# Sheet2.net
KiCad netlist of a schematic drawn in Altium Designer
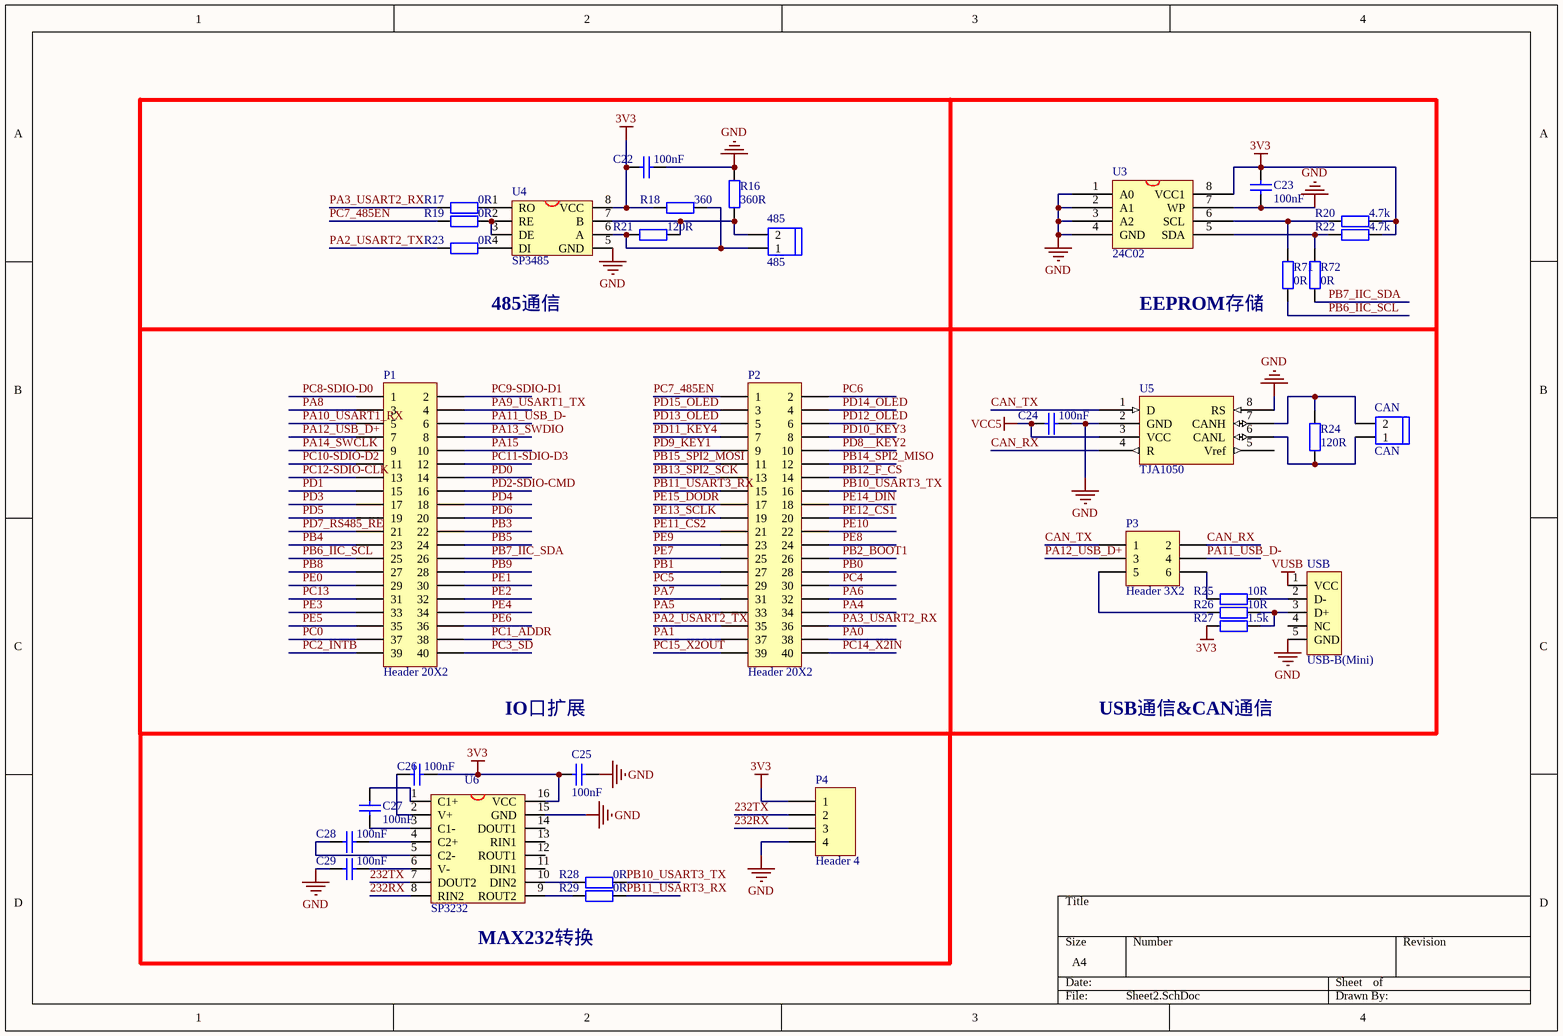
[diagram p0: Sheet2.SchDoc]

(export (version "E")
  (design (tool "Eeschema 10.0.6"))
  (components
    (comp (ref "485")
      (value "485")
      (footprint "HEAD2L-0.8")
      (libsource (lib "Explorer STM32F407封装库") (part "HEAD2"))
    )
    (comp (ref "C22")
      (value "100nF")
      (footprint "LC-0603_C")
      (description "无极性电容")
      (fields (field (name "PUBLISHER") "Altium Limited"))
      (libsource (lib "liu_2016") (part "Cap"))
    )
    (comp (ref "C23")
      (value "100nF")
      (footprint "LC-0603_C")
      (description "无极性电容")
      (fields (field (name "PUBLISHER") "Altium Limited"))
      (libsource (lib "liu_2016") (part "Cap"))
    )
    (comp (ref "C24")
      (value "100nF")
      (footprint "LC-0603_C")
      (description "无极性电容")
      (fields (field (name "PUBLISHER") "Altium Limited"))
      (libsource (lib "liu_2016") (part "Cap"))
    )
    (comp (ref "C25")
      (value "100nF")
      (footprint "LC-0603_C")
      (description "无极性电容")
      (fields (field (name "PUBLISHER") "Altium Limited"))
      (libsource (lib "liu_2016") (part "Cap"))
    )
    (comp (ref "C26")
      (value "100nF")
      (footprint "LC-0603_C")
      (description "无极性电容")
      (fields (field (name "PUBLISHER") "Altium Limited"))
      (libsource (lib "liu_2016") (part "Cap"))
    )
    (comp (ref "C27")
      (value "100nF")
      (footprint "LC-0603_C")
      (description "无极性电容")
      (fields (field (name "PUBLISHER") "Altium Limited"))
      (libsource (lib "liu_2016") (part "Cap"))
    )
    (comp (ref "C28")
      (value "100nF")
      (footprint "LC-0603_C")
      (description "无极性电容")
      (fields (field (name "PUBLISHER") "Altium Limited"))
      (libsource (lib "liu_2016") (part "Cap"))
    )
    (comp (ref "C29")
      (value "100nF")
      (footprint "LC-0603_C")
      (description "无极性电容")
      (fields (field (name "PUBLISHER") "Altium Limited"))
      (libsource (lib "liu_2016") (part "Cap"))
    )
    (comp (ref "CAN")
      (value "CAN")
      (footprint "CON_2_5.08B")
      (libsource (lib "Explorer STM32F407封装库") (part "HEAD2"))
    )
    (comp (ref "P1")
      (value "Header 20X2")
      (footprint "HDR2X20")
      (description "Header, 20-Pin, Dual row")
      (fields (field (name "PUBLISHER") "Altium Limited"))
      (libsource (lib "Sparks") (part "Header 20X2"))
    )
    (comp (ref "P2")
      (value "Header 20X2")
      (footprint "HDR2X20")
      (description "Header, 20-Pin, Dual row")
      (fields (field (name "PUBLISHER") "Altium Limited"))
      (libsource (lib "Sparks") (part "Header 20X2"))
    )
    (comp (ref "P3")
      (value "Header 3X2")
      (footprint "HDR2X3")
      (description "Header, 3-Pin, Dual row")
      (fields (field (name "PUBLISHER") "Altium Limited"))
      (libsource (lib "Sparks") (part "Header 3X2"))
    )
    (comp (ref "P4")
      (value "Header 4")
      (footprint "HDR1X4")
      (description "Header, 4-Pin")
      (fields (field (name "PUBLISHER") "Altium Limited"))
      (libsource (lib "Sparks") (part "Header 4"))
    )
    (comp (ref "R16")
      (value "360R")
      (footprint "LC-0603_R")
      (description "贴片电阻")
      (fields (field (name "PUBLISHER") "Altium Limited"))
      (libsource (lib "") (part "Res1_1"))
    )
    (comp (ref "R17")
      (value "0R")
      (footprint "LC-0603_R")
      (description "贴片电阻")
      (fields (field (name "PUBLISHER") "Altium Limited"))
      (libsource (lib "liu_2016") (part "Res1"))
    )
    (comp (ref "R18")
      (value "360")
      (footprint "LC-0603_R")
      (description "贴片电阻")
      (fields (field (name "PUBLISHER") "Altium Limited"))
      (libsource (lib "liu_2016") (part "Res1"))
    )
    (comp (ref "R19")
      (value "0R")
      (footprint "LC-0603_R")
      (description "贴片电阻")
      (fields (field (name "PUBLISHER") "Altium Limited"))
      (libsource (lib "liu_2016") (part "Res1"))
    )
    (comp (ref "R20")
      (value "4.7k")
      (footprint "LC-0603_R")
      (description "贴片电阻")
      (fields (field (name "PUBLISHER") "Altium Limited"))
      (libsource (lib "liu_2016") (part "Res1"))
    )
    (comp (ref "R21")
      (value "120R")
      (footprint "LC-0603_R")
      (description "贴片电阻")
      (fields (field (name "PUBLISHER") "Altium Limited"))
      (libsource (lib "liu_2016") (part "Res1"))
    )
    (comp (ref "R22")
      (value "4.7k")
      (footprint "LC-0603_R")
      (description "贴片电阻")
      (fields (field (name "PUBLISHER") "Altium Limited"))
      (libsource (lib "liu_2016") (part "Res1"))
    )
    (comp (ref "R23")
      (value "0R")
      (footprint "LC-0603_R")
      (description "贴片电阻")
      (fields (field (name "PUBLISHER") "Altium Limited"))
      (libsource (lib "liu_2016") (part "Res1"))
    )
    (comp (ref "R24")
      (value "120R")
      (footprint "LC-0603_R")
      (description "贴片电阻")
      (fields (field (name "PUBLISHER") "Altium Limited"))
      (libsource (lib "") (part "Res1_1"))
    )
    (comp (ref "R25")
      (value "10R")
      (footprint "LC-0603_R")
      (description "贴片电阻")
      (fields (field (name "PUBLISHER") "Altium Limited"))
      (libsource (lib "") (part "Res1_2"))
    )
    (comp (ref "R26")
      (value "10R")
      (footprint "LC-0603_R")
      (description "贴片电阻")
      (fields (field (name "PUBLISHER") "Altium Limited"))
      (libsource (lib "") (part "Res1_2"))
    )
    (comp (ref "R27")
      (value "1.5k")
      (footprint "LC-0603_R")
      (description "贴片电阻")
      (fields (field (name "PUBLISHER") "Altium Limited"))
      (libsource (lib "") (part "Res1_2"))
    )
    (comp (ref "R28")
      (value "0R")
      (footprint "LC-0603_R")
      (description "贴片电阻")
      (fields (field (name "PUBLISHER") "Altium Limited"))
      (libsource (lib "liu_2016") (part "Res1"))
    )
    (comp (ref "R29")
      (value "0R")
      (footprint "LC-0603_R")
      (description "贴片电阻")
      (fields (field (name "PUBLISHER") "Altium Limited"))
      (libsource (lib "liu_2016") (part "Res1"))
    )
    (comp (ref "R71")
      (value "0R")
      (footprint "LC-0603_R")
      (description "贴片电阻")
      (libsource (lib "Miscellaneous Devices LC") (part "0603 1.5KΩ (1501) 1%"))
    )
    (comp (ref "R72")
      (value "0R")
      (footprint "LC-0603_R")
      (description "贴片电阻")
      (libsource (lib "Miscellaneous Devices LC") (part "0603 1.5KΩ (1501) 1%"))
    )
    (comp (ref "U3")
      (value "24C02")
      (footprint "SO-8")
      (libsource (lib "Explorer STM32F407封装库") (part "24C256"))
    )
    (comp (ref "U4")
      (value "SP3485")
      (footprint "SO-8")
      (libsource (lib "Explorer STM32F407封装库") (part "MAX3485"))
    )
    (comp (ref "U5")
      (value "TJA1050")
      (footprint "SO-8")
      (libsource (lib "Explorer STM32F407封装库") (part "SN65HVD230D"))
    )
    (comp (ref "U6")
      (value "SP3232")
      (footprint "SO-16")
      (libsource (lib "Explorer STM32F407封装库") (part "MAX3232"))
    )
    (comp (ref "USB")
      (value "USB-B(Mini)")
      (footprint "USB/SM0.8-6H5")
      (libsource (lib "Explorer STM32F407封装库") (part "USB5"))
    )
  )
  (nets
    (net (code "1") (name "/232RX") (class "Default")
      (node (ref "P4") (pin "3") (pinfunction "3_3") (pintype "passive"))
      (node (ref "U6") (pin "8") (pinfunction "RIN2_8") (pintype "passive"))
    )
    (net (code "2") (name "/232TX") (class "Default")
      (node (ref "P4") (pin "2") (pinfunction "2_2") (pintype "passive"))
      (node (ref "U6") (pin "7") (pinfunction "DOUT2_7") (pintype "passive"))
    )
    (net (code "3") (name "/CAN_RX") (class "Default")
      (node (ref "P3") (pin "2") (pinfunction "2_2") (pintype "passive"))
      (node (ref "U5") (pin "4") (pinfunction "R_4") (pintype "output"))
    )
    (net (code "4") (name "/CAN_TX") (class "Default")
      (node (ref "P3") (pin "1") (pinfunction "1_1") (pintype "passive"))
      (node (ref "U5") (pin "1") (pinfunction "D_1") (pintype "input"))
    )
    (net (code "5") (name "/PA0") (class "Default")
      (node (ref "P2") (pin "38") (pinfunction "38_38") (pintype "passive"))
    )
    (net (code "6") (name "/PA1") (class "Default")
      (node (ref "P2") (pin "37") (pinfunction "37_37") (pintype "passive"))
    )
    (net (code "7") (name "/PA2_USART2_TX") (class "Default")
      (node (ref "P2") (pin "35") (pinfunction "35_35") (pintype "passive"))
      (node (ref "R23") (pin "2") (pinfunction "2_2") (pintype "passive"))
    )
    (net (code "8") (name "/PA3_USART2_RX") (class "Default")
      (node (ref "P2") (pin "36") (pinfunction "36_36") (pintype "passive"))
      (node (ref "R17") (pin "2") (pinfunction "2_2") (pintype "passive"))
    )
    (net (code "9") (name "/PA4") (class "Default")
      (node (ref "P2") (pin "34") (pinfunction "34_34") (pintype "passive"))
    )
    (net (code "10") (name "/PA5") (class "Default")
      (node (ref "P2") (pin "33") (pinfunction "33_33") (pintype "passive"))
    )
    (net (code "11") (name "/PA6") (class "Default")
      (node (ref "P2") (pin "32") (pinfunction "32_32") (pintype "passive"))
    )
    (net (code "12") (name "/PA7") (class "Default")
      (node (ref "P2") (pin "31") (pinfunction "31_31") (pintype "passive"))
    )
    (net (code "13") (name "/PA8") (class "Default")
      (node (ref "P1") (pin "3") (pinfunction "3_3") (pintype "passive"))
    )
    (net (code "14") (name "/PA9_USART1_TX") (class "Default")
      (node (ref "P1") (pin "4") (pinfunction "4_4") (pintype "passive"))
    )
    (net (code "15") (name "/PA10_USART1_RX") (class "Default")
      (node (ref "P1") (pin "5") (pinfunction "5_5") (pintype "passive"))
    )
    (net (code "16") (name "/PA11_USB_D-") (class "Default")
      (node (ref "P1") (pin "6") (pinfunction "6_6") (pintype "passive"))
      (node (ref "P3") (pin "4") (pinfunction "4_4") (pintype "passive"))
    )
    (net (code "17") (name "/PA12_USB_D+") (class "Default")
      (node (ref "P1") (pin "7") (pinfunction "7_7") (pintype "passive"))
      (node (ref "P3") (pin "3") (pinfunction "3_3") (pintype "passive"))
    )
    (net (code "18") (name "/PA13_SWDIO") (class "Default")
      (node (ref "P1") (pin "8") (pinfunction "8_8") (pintype "passive"))
    )
    (net (code "19") (name "/PA14_SWCLK") (class "Default")
      (node (ref "P1") (pin "9") (pinfunction "9_9") (pintype "passive"))
    )
    (net (code "20") (name "/PA15") (class "Default")
      (node (ref "P1") (pin "10") (pinfunction "10_10") (pintype "passive"))
    )
    (net (code "21") (name "/PB0") (class "Default")
      (node (ref "P2") (pin "28") (pinfunction "28_28") (pintype "passive"))
    )
    (net (code "22") (name "/PB1") (class "Default")
      (node (ref "P2") (pin "27") (pinfunction "27_27") (pintype "passive"))
    )
    (net (code "23") (name "/PB2_BOOT1") (class "Default")
      (node (ref "P2") (pin "26") (pinfunction "26_26") (pintype "passive"))
    )
    (net (code "24") (name "/PB3") (class "Default")
      (node (ref "P1") (pin "22") (pinfunction "22_22") (pintype "passive"))
    )
    (net (code "25") (name "/PB4") (class "Default")
      (node (ref "P1") (pin "23") (pinfunction "23_23") (pintype "passive"))
    )
    (net (code "26") (name "/PB5") (class "Default")
      (node (ref "P1") (pin "24") (pinfunction "24_24") (pintype "passive"))
    )
    (net (code "27") (name "/PB6_IIC_SCL") (class "Default")
      (node (ref "P1") (pin "25") (pinfunction "25_25") (pintype "passive"))
      (node (ref "R71") (pin "1") (pinfunction "1_1") (pintype "passive"))
    )
    (net (code "28") (name "/PB7_IIC_SDA") (class "Default")
      (node (ref "P1") (pin "26") (pinfunction "26_26") (pintype "passive"))
      (node (ref "R72") (pin "1") (pinfunction "1_1") (pintype "passive"))
    )
    (net (code "29") (name "/PB8") (class "Default")
      (node (ref "P1") (pin "27") (pinfunction "27_27") (pintype "passive"))
    )
    (net (code "30") (name "/PB9") (class "Default")
      (node (ref "P1") (pin "28") (pinfunction "28_28") (pintype "passive"))
    )
    (net (code "31") (name "/PB10_USART3_TX") (class "Default")
      (node (ref "P2") (pin "16") (pinfunction "16_16") (pintype "passive"))
      (node (ref "R28") (pin "1") (pinfunction "1_1") (pintype "passive"))
    )
    (net (code "32") (name "/PB11_USART3_RX") (class "Default")
      (node (ref "P2") (pin "15") (pinfunction "15_15") (pintype "passive"))
      (node (ref "R29") (pin "1") (pinfunction "1_1") (pintype "passive"))
    )
    (net (code "33") (name "/PB12_F_CS") (class "Default")
      (node (ref "P2") (pin "14") (pinfunction "14_14") (pintype "passive"))
    )
    (net (code "34") (name "/PB13_SPI2_SCK") (class "Default")
      (node (ref "P2") (pin "13") (pinfunction "13_13") (pintype "passive"))
    )
    (net (code "35") (name "/PB14_SPI2_MISO") (class "Default")
      (node (ref "P2") (pin "12") (pinfunction "12_12") (pintype "passive"))
    )
    (net (code "36") (name "/PB15_SPI2_MOSI") (class "Default")
      (node (ref "P2") (pin "11") (pinfunction "11_11") (pintype "passive"))
    )
    (net (code "37") (name "/PC0") (class "Default")
      (node (ref "P1") (pin "37") (pinfunction "37_37") (pintype "passive"))
    )
    (net (code "38") (name "/PC1_ADDR") (class "Default")
      (node (ref "P1") (pin "38") (pinfunction "38_38") (pintype "passive"))
    )
    (net (code "39") (name "/PC2_INTB") (class "Default")
      (node (ref "P1") (pin "39") (pinfunction "39_39") (pintype "passive"))
    )
    (net (code "40") (name "/PC3_SD") (class "Default")
      (node (ref "P1") (pin "40") (pinfunction "40_40") (pintype "passive"))
    )
    (net (code "41") (name "/PC4") (class "Default")
      (node (ref "P2") (pin "30") (pinfunction "30_30") (pintype "passive"))
    )
    (net (code "42") (name "/PC5") (class "Default")
      (node (ref "P2") (pin "29") (pinfunction "29_29") (pintype "passive"))
    )
    (net (code "43") (name "/PC6") (class "Default")
      (node (ref "P2") (pin "2") (pinfunction "2_2") (pintype "passive"))
    )
    (net (code "44") (name "/PC7_485EN") (class "Default")
      (node (ref "P2") (pin "1") (pinfunction "1_1") (pintype "passive"))
      (node (ref "R19") (pin "2") (pinfunction "2_2") (pintype "passive"))
    )
    (net (code "45") (name "/PC8-SDIO-D0") (class "Default")
      (node (ref "P1") (pin "1") (pinfunction "1_1") (pintype "passive"))
    )
    (net (code "46") (name "/PC9-SDIO-D1") (class "Default")
      (node (ref "P1") (pin "2") (pinfunction "2_2") (pintype "passive"))
    )
    (net (code "47") (name "/PC10-SDIO-D2") (class "Default")
      (node (ref "P1") (pin "11") (pinfunction "11_11") (pintype "passive"))
    )
    (net (code "48") (name "/PC11-SDIO-D3") (class "Default")
      (node (ref "P1") (pin "12") (pinfunction "12_12") (pintype "passive"))
    )
    (net (code "49") (name "/PC12-SDIO-CLK") (class "Default")
      (node (ref "P1") (pin "13") (pinfunction "13_13") (pintype "passive"))
    )
    (net (code "50") (name "/PC13") (class "Default")
      (node (ref "P1") (pin "31") (pinfunction "31_31") (pintype "passive"))
    )
    (net (code "51") (name "/PC14_X2IN") (class "Default")
      (node (ref "P2") (pin "40") (pinfunction "40_40") (pintype "passive"))
    )
    (net (code "52") (name "/PC15_X2OUT") (class "Default")
      (node (ref "P2") (pin "39") (pinfunction "39_39") (pintype "passive"))
    )
    (net (code "53") (name "/PD0") (class "Default")
      (node (ref "P1") (pin "14") (pinfunction "14_14") (pintype "passive"))
    )
    (net (code "54") (name "/PD1") (class "Default")
      (node (ref "P1") (pin "15") (pinfunction "15_15") (pintype "passive"))
    )
    (net (code "55") (name "/PD2-SDIO-CMD") (class "Default")
      (node (ref "P1") (pin "16") (pinfunction "16_16") (pintype "passive"))
    )
    (net (code "56") (name "/PD3") (class "Default")
      (node (ref "P1") (pin "17") (pinfunction "17_17") (pintype "passive"))
    )
    (net (code "57") (name "/PD4") (class "Default")
      (node (ref "P1") (pin "18") (pinfunction "18_18") (pintype "passive"))
    )
    (net (code "58") (name "/PD5") (class "Default")
      (node (ref "P1") (pin "19") (pinfunction "19_19") (pintype "passive"))
    )
    (net (code "59") (name "/PD6") (class "Default")
      (node (ref "P1") (pin "20") (pinfunction "20_20") (pintype "passive"))
    )
    (net (code "60") (name "/PD7_RS485_RE") (class "Default")
      (node (ref "P1") (pin "21") (pinfunction "21_21") (pintype "passive"))
    )
    (net (code "61") (name "/PD8__KEY2") (class "Default")
      (node (ref "P2") (pin "10") (pinfunction "10_10") (pintype "passive"))
    )
    (net (code "62") (name "/PD9_KEY1") (class "Default")
      (node (ref "P2") (pin "9") (pinfunction "9_9") (pintype "passive"))
    )
    (net (code "63") (name "/PD10_KEY3") (class "Default")
      (node (ref "P2") (pin "8") (pinfunction "8_8") (pintype "passive"))
    )
    (net (code "64") (name "/PD11_KEY4") (class "Default")
      (node (ref "P2") (pin "7") (pinfunction "7_7") (pintype "passive"))
    )
    (net (code "65") (name "/PD12_OLED") (class "Default")
      (node (ref "P2") (pin "6") (pinfunction "6_6") (pintype "passive"))
    )
    (net (code "66") (name "/PD13_OLED") (class "Default")
      (node (ref "P2") (pin "5") (pinfunction "5_5") (pintype "passive"))
    )
    (net (code "67") (name "/PD14_OLED") (class "Default")
      (node (ref "P2") (pin "4") (pinfunction "4_4") (pintype "passive"))
    )
    (net (code "68") (name "/PD15_OLED") (class "Default")
      (node (ref "P2") (pin "3") (pinfunction "3_3") (pintype "passive"))
    )
    (net (code "69") (name "/PE0") (class "Default")
      (node (ref "P1") (pin "29") (pinfunction "29_29") (pintype "passive"))
    )
    (net (code "70") (name "/PE1") (class "Default")
      (node (ref "P1") (pin "30") (pinfunction "30_30") (pintype "passive"))
    )
    (net (code "71") (name "/PE2") (class "Default")
      (node (ref "P1") (pin "32") (pinfunction "32_32") (pintype "passive"))
    )
    (net (code "72") (name "/PE3") (class "Default")
      (node (ref "P1") (pin "33") (pinfunction "33_33") (pintype "passive"))
    )
    (net (code "73") (name "/PE4") (class "Default")
      (node (ref "P1") (pin "34") (pinfunction "34_34") (pintype "passive"))
    )
    (net (code "74") (name "/PE5") (class "Default")
      (node (ref "P1") (pin "35") (pinfunction "35_35") (pintype "passive"))
    )
    (net (code "75") (name "/PE6") (class "Default")
      (node (ref "P1") (pin "36") (pinfunction "36_36") (pintype "passive"))
    )
    (net (code "76") (name "/PE7") (class "Default")
      (node (ref "P2") (pin "25") (pinfunction "25_25") (pintype "passive"))
    )
    (net (code "77") (name "/PE8") (class "Default")
      (node (ref "P2") (pin "24") (pinfunction "24_24") (pintype "passive"))
    )
    (net (code "78") (name "/PE9") (class "Default")
      (node (ref "P2") (pin "23") (pinfunction "23_23") (pintype "passive"))
    )
    (net (code "79") (name "/PE10") (class "Default")
      (node (ref "P2") (pin "22") (pinfunction "22_22") (pintype "passive"))
    )
    (net (code "80") (name "/PE11_CS2") (class "Default")
      (node (ref "P2") (pin "21") (pinfunction "21_21") (pintype "passive"))
    )
    (net (code "81") (name "/PE12_CS1") (class "Default")
      (node (ref "P2") (pin "20") (pinfunction "20_20") (pintype "passive"))
    )
    (net (code "82") (name "/PE13_SCLK") (class "Default")
      (node (ref "P2") (pin "19") (pinfunction "19_19") (pintype "passive"))
    )
    (net (code "83") (name "/PE14_DIN") (class "Default")
      (node (ref "P2") (pin "18") (pinfunction "18_18") (pintype "passive"))
    )
    (net (code "84") (name "/PE15_DODR") (class "Default")
      (node (ref "P2") (pin "17") (pinfunction "17_17") (pintype "passive"))
    )
    (net (code "85") (name "3V3") (class "Default")
      (node (ref "C22") (pin "1") (pinfunction "1_1") (pintype "passive"))
      (node (ref "C23") (pin "1") (pinfunction "1_1") (pintype "passive"))
      (node (ref "C25") (pin "2") (pinfunction "2_2") (pintype "passive"))
      (node (ref "C26") (pin "1") (pinfunction "1_1") (pintype "passive"))
      (node (ref "P4") (pin "1") (pinfunction "1_1") (pintype "passive"))
      (node (ref "R18") (pin "2") (pinfunction "2_2") (pintype "passive"))
      (node (ref "R20") (pin "1") (pinfunction "1_1") (pintype "passive"))
      (node (ref "R22") (pin "1") (pinfunction "1_1") (pintype "passive"))
      (node (ref "R27") (pin "1") (pinfunction "1_1") (pintype "passive"))
      (node (ref "U3") (pin "8") (pinfunction "VCC1_8") (pintype "passive"))
      (node (ref "U4") (pin "8") (pinfunction "VCC_8") (pintype "passive"))
      (node (ref "U6") (pin "16") (pinfunction "VCC_16") (pintype "passive"))
    )
    (net (code "86") (name "GND") (class "Default")
      (node (ref "C22") (pin "2") (pinfunction "2_2") (pintype "passive"))
      (node (ref "C23") (pin "2") (pinfunction "2_2") (pintype "passive"))
      (node (ref "C24") (pin "2") (pinfunction "2_2") (pintype "passive"))
      (node (ref "C25") (pin "1") (pinfunction "1_1") (pintype "passive"))
      (node (ref "C29") (pin "2") (pinfunction "2_2") (pintype "passive"))
      (node (ref "P4") (pin "4") (pinfunction "4_4") (pintype "passive"))
      (node (ref "R16") (pin "1") (pinfunction "1_1") (pintype "passive"))
      (node (ref "U3") (pin "1") (pinfunction "A0_1") (pintype "passive"))
      (node (ref "U3") (pin "2") (pinfunction "A1_2") (pintype "passive"))
      (node (ref "U3") (pin "3") (pinfunction "A2_3") (pintype "passive"))
      (node (ref "U3") (pin "4") (pinfunction "GND_4") (pintype "passive"))
      (node (ref "U3") (pin "7") (pinfunction "WP_7") (pintype "passive"))
      (node (ref "U4") (pin "5") (pinfunction "GND_5") (pintype "passive"))
      (node (ref "U5") (pin "2") (pinfunction "GND_2") (pintype "power_in"))
      (node (ref "U5") (pin "8") (pinfunction "RS_8") (pintype "input"))
      (node (ref "U6") (pin "15") (pinfunction "GND_15") (pintype "passive"))
      (node (ref "USB") (pin "5") (pinfunction "GND_5") (pintype "passive"))
    )
    (net (code "87") (name "Net-(P3-Pad5)") (class "Default")
      (node (ref "P3") (pin "5") (pinfunction "5_5") (pintype "passive"))
      (node (ref "R26") (pin "1") (pinfunction "1_1") (pintype "passive"))
    )
    (net (code "88") (name "Net-(P3-Pad6)") (class "Default")
      (node (ref "P3") (pin "6") (pinfunction "6_6") (pintype "passive"))
      (node (ref "R25") (pin "1") (pinfunction "1_1") (pintype "passive"))
    )
    (net (code "89") (name "Net-(U3-SCL)") (class "Default")
      (node (ref "R20") (pin "2") (pinfunction "2_2") (pintype "passive"))
      (node (ref "R71") (pin "2") (pinfunction "2_2") (pintype "passive"))
      (node (ref "U3") (pin "6") (pinfunction "SCL_6") (pintype "passive"))
    )
    (net (code "90") (name "Net-(U3-SDA)") (class "Default")
      (node (ref "R22") (pin "2") (pinfunction "2_2") (pintype "passive"))
      (node (ref "R72") (pin "2") (pinfunction "2_2") (pintype "passive"))
      (node (ref "U3") (pin "5") (pinfunction "SDA_5") (pintype "passive"))
    )
    (net (code "91") (name "Net-(U4-A)") (class "Default")
      (node (ref "485") (pin "1") (pinfunction "1_1") (pintype "passive"))
      (node (ref "R18") (pin "1") (pinfunction "1_1") (pintype "passive"))
      (node (ref "R21") (pin "2") (pinfunction "2_2") (pintype "passive"))
      (node (ref "U4") (pin "6") (pinfunction "A_6") (pintype "passive"))
    )
    (net (code "92") (name "Net-(U4-B)") (class "Default")
      (node (ref "485") (pin "2") (pinfunction "2_2") (pintype "passive"))
      (node (ref "R16") (pin "2") (pinfunction "2_2") (pintype "passive"))
      (node (ref "R21") (pin "1") (pinfunction "1_1") (pintype "passive"))
      (node (ref "U4") (pin "7") (pinfunction "B_7") (pintype "passive"))
    )
    (net (code "93") (name "Net-(U4-DE)") (class "Default")
      (node (ref "R19") (pin "1") (pinfunction "1_1") (pintype "passive"))
      (node (ref "U4") (pin "2") (pinfunction "RE_2") (pintype "passive"))
      (node (ref "U4") (pin "3") (pinfunction "DE_3") (pintype "passive"))
    )
    (net (code "94") (name "Net-(U4-DI)") (class "Default")
      (node (ref "R23") (pin "1") (pinfunction "1_1") (pintype "passive"))
      (node (ref "U4") (pin "4") (pinfunction "DI_4") (pintype "passive"))
    )
    (net (code "95") (name "Net-(U4-RO)") (class "Default")
      (node (ref "R17") (pin "1") (pinfunction "1_1") (pintype "passive"))
      (node (ref "U4") (pin "1") (pinfunction "RO_1") (pintype "passive"))
    )
    (net (code "96") (name "Net-(U5-CANH)") (class "Default")
      (node (ref "CAN") (pin "2") (pinfunction "2_2") (pintype "passive"))
      (node (ref "R24") (pin "1") (pinfunction "1_1") (pintype "passive"))
      (node (ref "U5") (pin "7") (pinfunction "CANH_7") (pintype "bidirectional"))
    )
    (net (code "97") (name "Net-(U5-CANL)") (class "Default")
      (node (ref "CAN") (pin "1") (pinfunction "1_1") (pintype "passive"))
      (node (ref "R24") (pin "2") (pinfunction "2_2") (pintype "passive"))
      (node (ref "U5") (pin "6") (pinfunction "CANL_6") (pintype "bidirectional"))
    )
    (net (code "98") (name "Net-(U6-C1+)") (class "Default")
      (node (ref "C27") (pin "2") (pinfunction "2_2") (pintype "passive"))
      (node (ref "U6") (pin "1") (pinfunction "C1+_1") (pintype "passive"))
    )
    (net (code "99") (name "Net-(U6-C1-)") (class "Default")
      (node (ref "C27") (pin "1") (pinfunction "1_1") (pintype "passive"))
      (node (ref "U6") (pin "3") (pinfunction "C1-_3") (pintype "passive"))
    )
    (net (code "100") (name "Net-(U6-C2+)") (class "Default")
      (node (ref "C28") (pin "2") (pinfunction "2_2") (pintype "passive"))
      (node (ref "U6") (pin "4") (pinfunction "C2+_4") (pintype "passive"))
    )
    (net (code "101") (name "Net-(U6-C2-)") (class "Default")
      (node (ref "C28") (pin "1") (pinfunction "1_1") (pintype "passive"))
      (node (ref "U6") (pin "5") (pinfunction "C2-_5") (pintype "passive"))
    )
    (net (code "102") (name "Net-(U6-DIN2)") (class "Default")
      (node (ref "R28") (pin "2") (pinfunction "2_2") (pintype "passive"))
      (node (ref "U6") (pin "10") (pinfunction "DIN2_10") (pintype "passive"))
    )
    (net (code "103") (name "Net-(U6-ROUT2)") (class "Default")
      (node (ref "R29") (pin "2") (pinfunction "2_2") (pintype "passive"))
      (node (ref "U6") (pin "9") (pinfunction "ROUT2_9") (pintype "passive"))
    )
    (net (code "104") (name "Net-(U6-V+)") (class "Default")
      (node (ref "C26") (pin "2") (pinfunction "2_2") (pintype "passive"))
      (node (ref "U6") (pin "2") (pinfunction "V+_2") (pintype "passive"))
    )
    (net (code "105") (name "Net-(U6-V-)") (class "Default")
      (node (ref "C29") (pin "1") (pinfunction "1_1") (pintype "passive"))
      (node (ref "U6") (pin "6") (pinfunction "V-_6") (pintype "passive"))
    )
    (net (code "106") (name "Net-(USB-D+)") (class "Default")
      (node (ref "R26") (pin "2") (pinfunction "2_2") (pintype "passive"))
      (node (ref "R27") (pin "2") (pinfunction "2_2") (pintype "passive"))
      (node (ref "USB") (pin "3") (pinfunction "D+_3") (pintype "passive"))
    )
    (net (code "107") (name "Net-(USB-D-)") (class "Default")
      (node (ref "R25") (pin "2") (pinfunction "2_2") (pintype "passive"))
      (node (ref "USB") (pin "2") (pinfunction "D-_2") (pintype "passive"))
    )
    (net (code "108") (name "VCC5") (class "Default")
      (node (ref "C24") (pin "1") (pinfunction "1_1") (pintype "passive"))
      (node (ref "U5") (pin "3") (pinfunction "VCC_3") (pintype "power_in"))
    )
    (net (code "109") (name "VUSB") (class "Default")
      (node (ref "USB") (pin "1") (pinfunction "VCC_1") (pintype "passive"))
    )
    (net (code "110") (name "unconnected-(U5-Vref-Pad5)") (class "Default")
      (node (ref "U5") (pin "5") (pinfunction "Vref_5") (pintype "output"))
    )
    (net (code "111") (name "unconnected-(U6-DIN1-Pad11)") (class "Default")
      (node (ref "U6") (pin "11") (pinfunction "DIN1_11") (pintype "passive"))
    )
    (net (code "112") (name "unconnected-(U6-DOUT1-Pad14)") (class "Default")
      (node (ref "U6") (pin "14") (pinfunction "DOUT1_14") (pintype "passive"))
    )
    (net (code "113") (name "unconnected-(U6-RIN1-Pad13)") (class "Default")
      (node (ref "U6") (pin "13") (pinfunction "RIN1_13") (pintype "passive"))
    )
    (net (code "114") (name "unconnected-(U6-ROUT1-Pad12)") (class "Default")
      (node (ref "U6") (pin "12") (pinfunction "ROUT1_12") (pintype "passive"))
    )
    (net (code "115") (name "unconnected-(USB-NC-Pad4)") (class "Default")
      (node (ref "USB") (pin "4") (pinfunction "NC_4") (pintype "passive"))
    )
  )
)
